# Load_Cell_Acquisition.net
KiCad netlist of a schematic drawn in Altium Designer
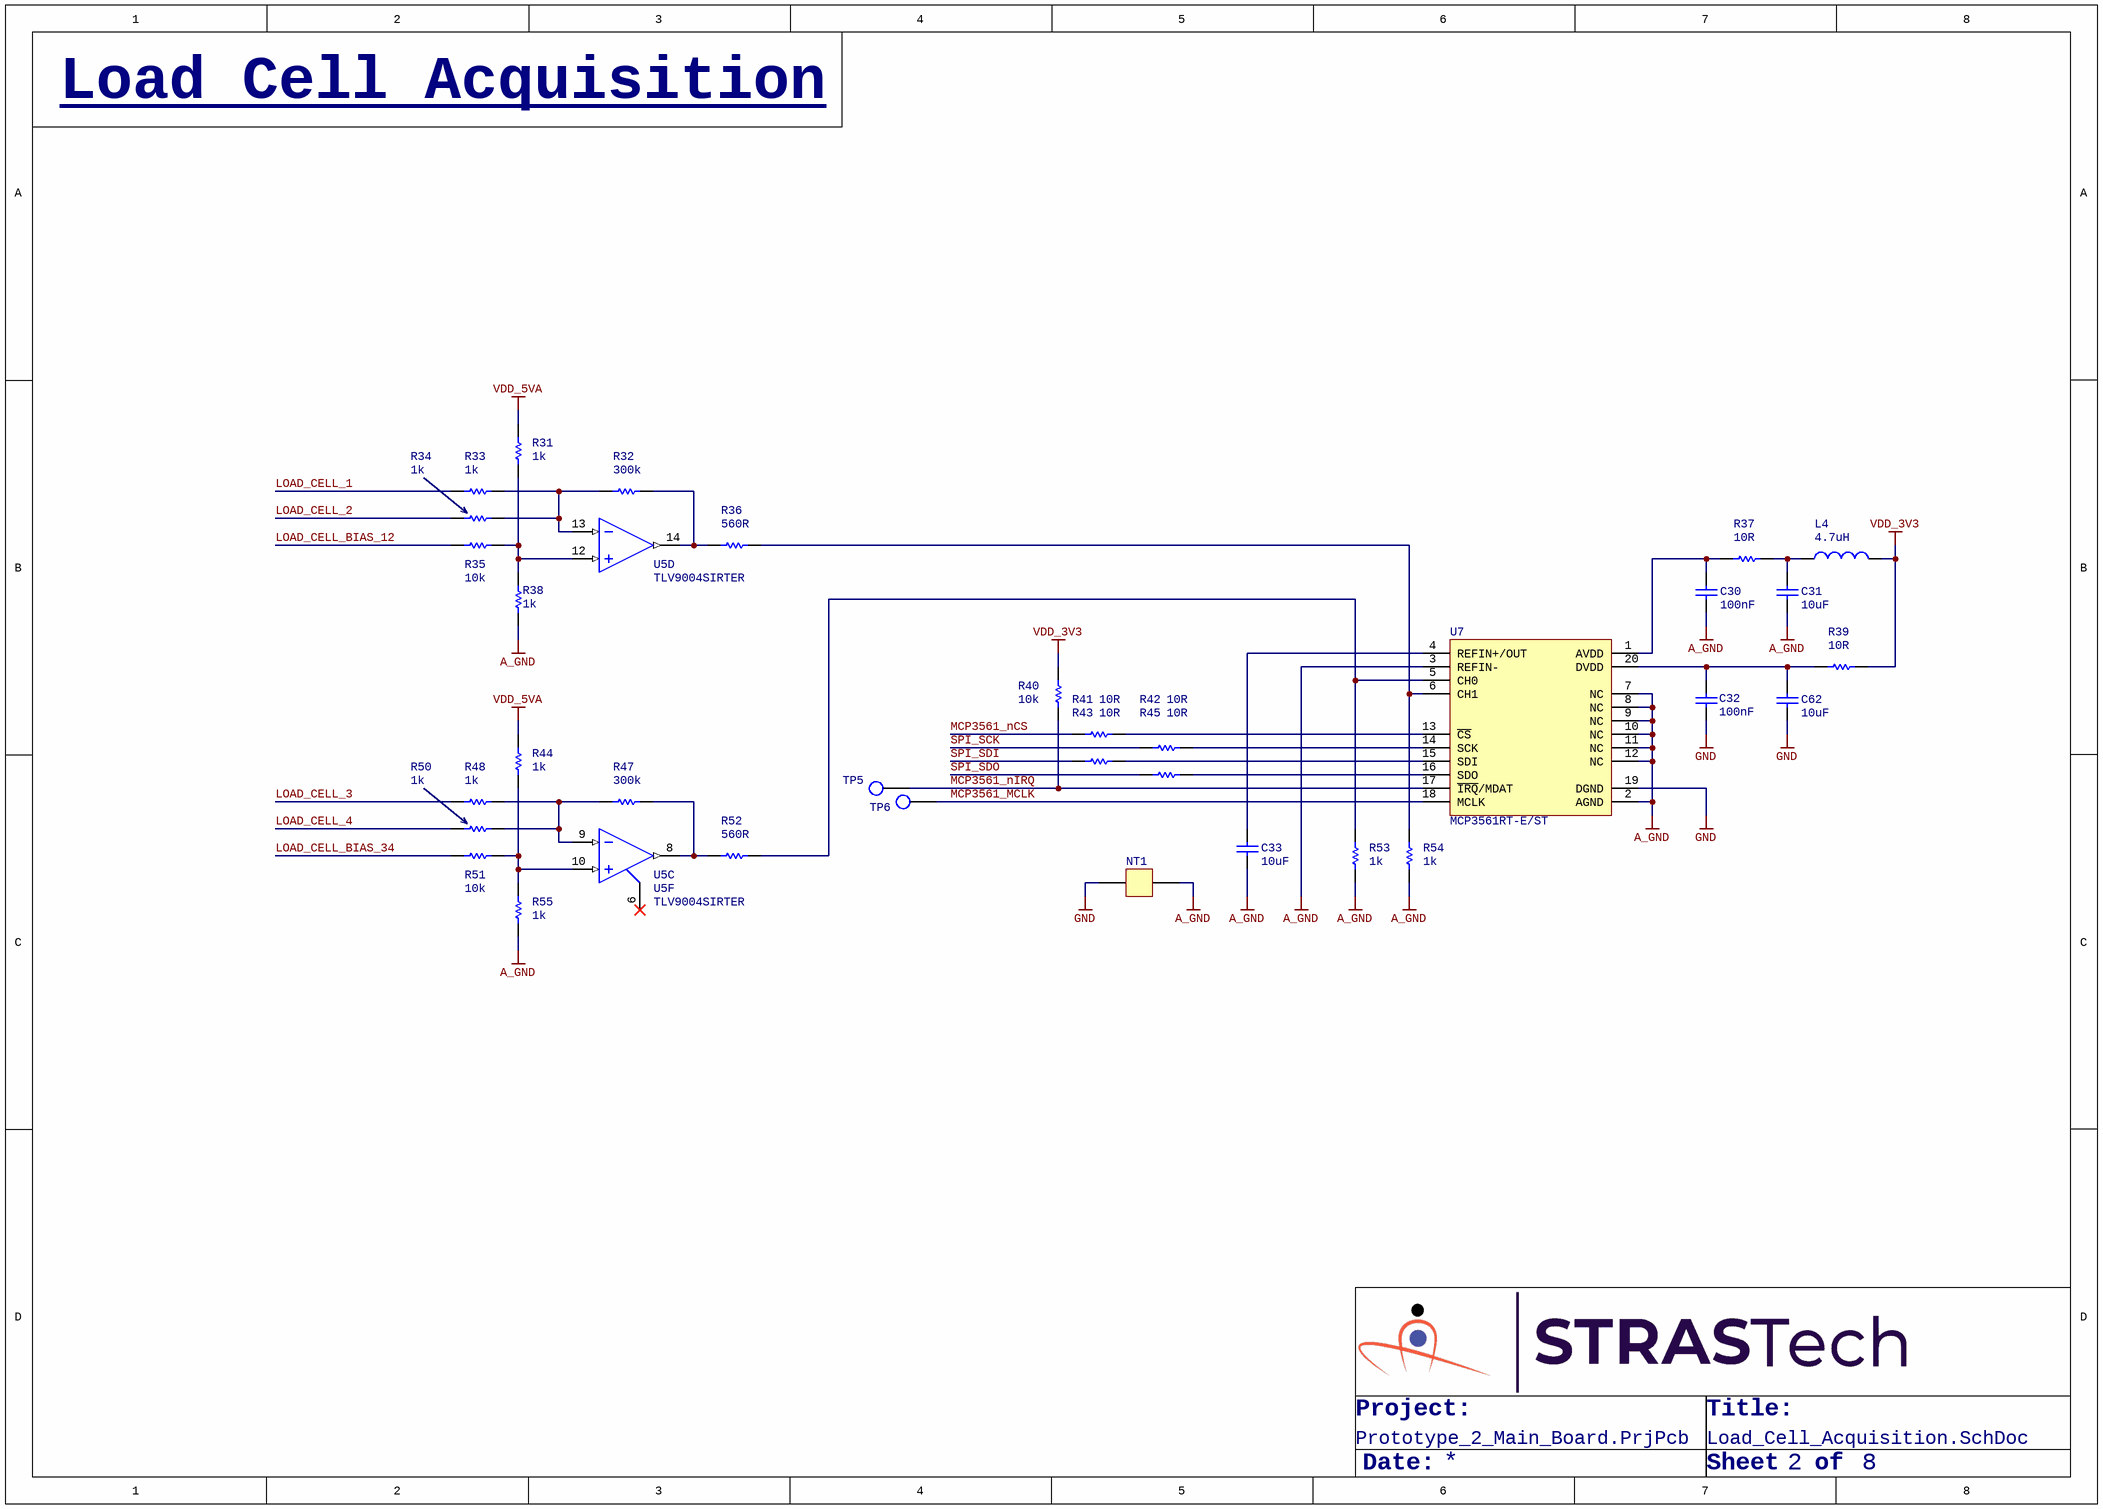
[diagram p0: Load_Cell_Acquisition.SchDoc]

(export (version "E")
  (design (tool "Eeschema 10.0.6"))
  (components
    (comp (ref "C30")
      (value "100nF")
      (footprint "Cap,SMD,0402")
      (description "0.1µF ±10% 25V Ceramic Capacitor X7R 0402 (1005 Metric)")
      (fields
        (field (name "VENDOR PART NUMBER") "490-14603-1-ND")
        (field (name "MANUFACTURER") "Murata Electronics")
        (field (name "CREATEDBY") "Judd Foster")
      )
      (libsource (lib "symbols") (part "CAP,Cer,100nF,25VDC,X7R,0402"))
    )
    (comp (ref "C31")
      (value "10uF")
      (footprint "Cap,SMD,0402")
      (description "10 µF ±20% 10V Ceramic Capacitor X5R 0402 (1005 Metric)")
      (fields
        (field (name "VENDOR PART NUMBER") "1276-1450-1-ND")
        (field (name "MANUFACTURER") "Samsung Electro-Mechanics")
        (field (name "CREATEDBY") "Judd Foster")
      )
      (libsource (lib "symbols") (part "CAP,Cer,10uF,10VDC,X5R,0402"))
    )
    (comp (ref "C32")
      (value "100nF")
      (footprint "Cap,SMD,0402")
      (description "0.1µF ±10% 25V Ceramic Capacitor X7R 0402 (1005 Metric)")
      (fields
        (field (name "VENDOR PART NUMBER") "490-14603-1-ND")
        (field (name "MANUFACTURER") "Murata Electronics")
        (field (name "CREATEDBY") "Judd Foster")
      )
      (libsource (lib "symbols") (part "CAP,Cer,100nF,25VDC,X7R,0402"))
    )
    (comp (ref "C33")
      (value "10uF")
      (footprint "Cap,SMD,0402")
      (description "10 µF ±20% 10V Ceramic Capacitor X5R 0402 (1005 Metric)")
      (fields
        (field (name "VENDOR PART NUMBER") "1276-1450-1-ND")
        (field (name "MANUFACTURER") "Samsung Electro-Mechanics")
        (field (name "CREATEDBY") "Judd Foster")
      )
      (libsource (lib "symbols") (part "CAP,Cer,10uF,10VDC,X5R,0402"))
    )
    (comp (ref "C62")
      (value "10uF")
      (footprint "Cap,SMD,0402")
      (description "10 µF ±20% 10V Ceramic Capacitor X5R 0402 (1005 Metric)")
      (fields
        (field (name "VENDOR PART NUMBER") "1276-1450-1-ND")
        (field (name "MANUFACTURER") "Samsung Electro-Mechanics")
        (field (name "CREATEDBY") "Judd Foster")
      )
      (libsource (lib "symbols") (part "CAP,Cer,10uF,10VDC,X5R,0402"))
    )
    (comp (ref "L4")
      (value "4.7uH")
      (footprint "IND,0805")
      (description "4.7 µH Shielded Multilayer Inductor 80 mA 300mOhm 0805 (2012 Metric)")
      (fields
        (field (name "VENDOR PART NUMBER") "445-3169-1-ND")
        (field (name "MANUFACTURER") "TDK Corporation")
        (field (name "CREATEDBY") "Judd Foster")
      )
      (libsource (lib "symbols") (part "IND,4.7uH,80mA,Multilayer,0805"))
    )
    (comp (ref "NT1")
      (value "Net Tie")
      (footprint "Net Tie,20x60mil")
      (fields (field (name "CREATEDBY") "Makan Mousavi"))
      (libsource (lib "symbols") (part "Net Tie"))
    )
    (comp (ref "R31")
      (value "1k")
      (footprint "RES,0402")
      (description "1 kOhms ±5% 0.063W, 1/16W Chip Resistor 0402 (1005 Metric) Automotive AEC-Q200 Thick Film")
      (fields
        (field (name "VENDOR PART NUMBER") "RMCF0402JT1K00CT-ND")
        (field (name "MANUFACTURER") "Stackpole Electronics Inc")
        (field (name "CREATEDBY") "Judd Foster")
      )
      (libsource (lib "symbols") (part "RES,1k,5%,0.063W,0402"))
    )
    (comp (ref "R32")
      (value "300k")
      (footprint "RES,0402")
      (description "300 kOhms ±1% 0.063W, 1/16W Chip Resistor 0402 (1005 Metric) Automotive AEC-Q200 Thick Film")
      (fields
        (field (name "MANUFACTURER") "Stackpole Electronics Inc")
        (field (name "MANUFACTURER PART NUMBER") "RMCF0402FT300K")
        (field (name "CREATEDBY") "Judd Foster")
      )
      (libsource (lib "symbols") (part "RES,300k,1%,0.063W,0402"))
    )
    (comp (ref "R33")
      (value "1k")
      (footprint "RES,0402")
      (description "1 kOhms ±5% 0.063W, 1/16W Chip Resistor 0402 (1005 Metric) Automotive AEC-Q200 Thick Film")
      (fields
        (field (name "VENDOR PART NUMBER") "RMCF0402JT1K00CT-ND")
        (field (name "MANUFACTURER") "Stackpole Electronics Inc")
        (field (name "CREATEDBY") "Judd Foster")
      )
      (libsource (lib "symbols") (part "RES,1k,5%,0.063W,0402"))
    )
    (comp (ref "R34")
      (value "1k")
      (footprint "RES,0402")
      (description "1 kOhms ±5% 0.063W, 1/16W Chip Resistor 0402 (1005 Metric) Automotive AEC-Q200 Thick Film")
      (fields
        (field (name "VENDOR PART NUMBER") "RMCF0402JT1K00CT-ND")
        (field (name "MANUFACTURER") "Stackpole Electronics Inc")
        (field (name "CREATEDBY") "Judd Foster")
      )
      (libsource (lib "symbols") (part "RES,1k,5%,0.063W,0402"))
    )
    (comp (ref "R35")
      (value "10k")
      (footprint "RES,0402")
      (description "10 kOhms ±5% 0.063W, 1/16W Chip Resistor 0402 (1005 Metric) Automotive AEC-Q200 Thick Film")
      (fields
        (field (name "VENDOR PART NUMBER") "RMCF0402JT10K0CT-ND")
        (field (name "MANUFACTURER") "Stackpole Electronics Inc")
        (field (name "CREATEDBY") "Judd Foster")
      )
      (libsource (lib "symbols") (part "RES,10k,5%,0.063W,0402"))
    )
    (comp (ref "R36")
      (value "560R")
      (footprint "RES,0402")
      (fields
        (field (name "MANUFACTURER") "TE Connectivity Passive Product")
        (field (name "MANUFACTURER PART NUMBER") "CRGCQ0402F560R")
        (field (name "VENDOR PART NUMBER") "A129624CT-ND")
        (field (name "CREATEDBY") "Judd Foster")
      )
      (libsource (lib "symbols") (part "RES,560R,1%,0.063W,0402"))
    )
    (comp (ref "R37")
      (value "10R")
      (footprint "RES,0402")
      (description "10 Ohms ±1% 0.063W, 1/16W Chip Resistor 0402 (1005 Metric) Automotive AEC-Q200 Thick Film")
      (fields
        (field (name "MANUFACTURER") "Panasonic Electronic Components")
        (field (name "MANUFACTURER PART NUMBER") "ERJ-2RKF10R0X")
        (field (name "CREATEDBY") "Judd Foster")
      )
      (libsource (lib "symbols") (part "RES,10R,1%,0.063W,0402"))
    )
    (comp (ref "R38")
      (value "1k")
      (footprint "RES,0402")
      (description "1 kOhms ±5% 0.063W, 1/16W Chip Resistor 0402 (1005 Metric) Automotive AEC-Q200 Thick Film")
      (fields
        (field (name "VENDOR PART NUMBER") "RMCF0402JT1K00CT-ND")
        (field (name "MANUFACTURER") "Stackpole Electronics Inc")
        (field (name "CREATEDBY") "Judd Foster")
      )
      (libsource (lib "symbols") (part "RES,1k,5%,0.063W,0402"))
    )
    (comp (ref "R39")
      (value "10R")
      (footprint "RES,0402")
      (description "10 Ohms ±1% 0.063W, 1/16W Chip Resistor 0402 (1005 Metric) Automotive AEC-Q200 Thick Film")
      (fields
        (field (name "MANUFACTURER") "Panasonic Electronic Components")
        (field (name "MANUFACTURER PART NUMBER") "ERJ-2RKF10R0X")
        (field (name "CREATEDBY") "Judd Foster")
      )
      (libsource (lib "symbols") (part "RES,10R,1%,0.063W,0402"))
    )
    (comp (ref "R40")
      (value "10k")
      (footprint "RES,0402")
      (description "10 kOhms ±5% 0.063W, 1/16W Chip Resistor 0402 (1005 Metric) Automotive AEC-Q200 Thick Film")
      (fields
        (field (name "VENDOR PART NUMBER") "RMCF0402JT10K0CT-ND")
        (field (name "MANUFACTURER") "Stackpole Electronics Inc")
        (field (name "CREATEDBY") "Judd Foster")
      )
      (libsource (lib "symbols") (part "RES,10k,5%,0.063W,0402"))
    )
    (comp (ref "R41")
      (value "10R")
      (footprint "RES,0402")
      (description "10 Ohms ±1% 0.063W, 1/16W Chip Resistor 0402 (1005 Metric) Automotive AEC-Q200 Thick Film")
      (fields
        (field (name "MANUFACTURER") "Panasonic Electronic Components")
        (field (name "MANUFACTURER PART NUMBER") "ERJ-2RKF10R0X")
        (field (name "CREATEDBY") "Judd Foster")
      )
      (libsource (lib "symbols") (part "RES,10R,1%,0.063W,0402"))
    )
    (comp (ref "R42")
      (value "10R")
      (footprint "RES,0402")
      (description "10 Ohms ±1% 0.063W, 1/16W Chip Resistor 0402 (1005 Metric) Automotive AEC-Q200 Thick Film")
      (fields
        (field (name "MANUFACTURER") "Panasonic Electronic Components")
        (field (name "MANUFACTURER PART NUMBER") "ERJ-2RKF10R0X")
        (field (name "CREATEDBY") "Judd Foster")
      )
      (libsource (lib "symbols") (part "RES,10R,1%,0.063W,0402"))
    )
    (comp (ref "R43")
      (value "10R")
      (footprint "RES,0402")
      (description "10 Ohms ±1% 0.063W, 1/16W Chip Resistor 0402 (1005 Metric) Automotive AEC-Q200 Thick Film")
      (fields
        (field (name "MANUFACTURER") "Panasonic Electronic Components")
        (field (name "MANUFACTURER PART NUMBER") "ERJ-2RKF10R0X")
        (field (name "CREATEDBY") "Judd Foster")
      )
      (libsource (lib "symbols") (part "RES,10R,1%,0.063W,0402"))
    )
    (comp (ref "R44")
      (value "1k")
      (footprint "RES,0402")
      (description "1 kOhms ±5% 0.063W, 1/16W Chip Resistor 0402 (1005 Metric) Automotive AEC-Q200 Thick Film")
      (fields
        (field (name "VENDOR PART NUMBER") "RMCF0402JT1K00CT-ND")
        (field (name "MANUFACTURER") "Stackpole Electronics Inc")
        (field (name "CREATEDBY") "Judd Foster")
      )
      (libsource (lib "symbols") (part "RES,1k,5%,0.063W,0402"))
    )
    (comp (ref "R45")
      (value "10R")
      (footprint "RES,0402")
      (description "10 Ohms ±1% 0.063W, 1/16W Chip Resistor 0402 (1005 Metric) Automotive AEC-Q200 Thick Film")
      (fields
        (field (name "MANUFACTURER") "Panasonic Electronic Components")
        (field (name "MANUFACTURER PART NUMBER") "ERJ-2RKF10R0X")
        (field (name "CREATEDBY") "Judd Foster")
      )
      (libsource (lib "symbols") (part "RES,10R,1%,0.063W,0402"))
    )
    (comp (ref "R47")
      (value "300k")
      (footprint "RES,0402")
      (description "300 kOhms ±1% 0.063W, 1/16W Chip Resistor 0402 (1005 Metric) Automotive AEC-Q200 Thick Film")
      (fields
        (field (name "MANUFACTURER") "Stackpole Electronics Inc")
        (field (name "MANUFACTURER PART NUMBER") "RMCF0402FT300K")
        (field (name "CREATEDBY") "Judd Foster")
      )
      (libsource (lib "symbols") (part "RES,300k,1%,0.063W,0402"))
    )
    (comp (ref "R48")
      (value "1k")
      (footprint "RES,0402")
      (description "1 kOhms ±5% 0.063W, 1/16W Chip Resistor 0402 (1005 Metric) Automotive AEC-Q200 Thick Film")
      (fields
        (field (name "VENDOR PART NUMBER") "RMCF0402JT1K00CT-ND")
        (field (name "MANUFACTURER") "Stackpole Electronics Inc")
        (field (name "CREATEDBY") "Judd Foster")
      )
      (libsource (lib "symbols") (part "RES,1k,5%,0.063W,0402"))
    )
    (comp (ref "R50")
      (value "1k")
      (footprint "RES,0402")
      (description "1 kOhms ±5% 0.063W, 1/16W Chip Resistor 0402 (1005 Metric) Automotive AEC-Q200 Thick Film")
      (fields
        (field (name "VENDOR PART NUMBER") "RMCF0402JT1K00CT-ND")
        (field (name "MANUFACTURER") "Stackpole Electronics Inc")
        (field (name "CREATEDBY") "Judd Foster")
      )
      (libsource (lib "symbols") (part "RES,1k,5%,0.063W,0402"))
    )
    (comp (ref "R51")
      (value "10k")
      (footprint "RES,0402")
      (description "10 kOhms ±5% 0.063W, 1/16W Chip Resistor 0402 (1005 Metric) Automotive AEC-Q200 Thick Film")
      (fields
        (field (name "VENDOR PART NUMBER") "RMCF0402JT10K0CT-ND")
        (field (name "MANUFACTURER") "Stackpole Electronics Inc")
        (field (name "CREATEDBY") "Judd Foster")
      )
      (libsource (lib "symbols") (part "RES,10k,5%,0.063W,0402"))
    )
    (comp (ref "R52")
      (value "560R")
      (footprint "RES,0402")
      (fields
        (field (name "MANUFACTURER") "TE Connectivity Passive Product")
        (field (name "MANUFACTURER PART NUMBER") "CRGCQ0402F560R")
        (field (name "VENDOR PART NUMBER") "A129624CT-ND")
        (field (name "CREATEDBY") "Judd Foster")
      )
      (libsource (lib "symbols") (part "RES,560R,1%,0.063W,0402"))
    )
    (comp (ref "R53")
      (value "1k")
      (footprint "RES,0402")
      (description "1 kOhms ±5% 0.063W, 1/16W Chip Resistor 0402 (1005 Metric) Automotive AEC-Q200 Thick Film")
      (fields
        (field (name "VENDOR PART NUMBER") "RMCF0402JT1K00CT-ND")
        (field (name "MANUFACTURER") "Stackpole Electronics Inc")
        (field (name "CREATEDBY") "Judd Foster")
      )
      (libsource (lib "symbols") (part "RES,1k,5%,0.063W,0402"))
    )
    (comp (ref "R54")
      (value "1k")
      (footprint "RES,0402")
      (description "1 kOhms ±5% 0.063W, 1/16W Chip Resistor 0402 (1005 Metric) Automotive AEC-Q200 Thick Film")
      (fields
        (field (name "VENDOR PART NUMBER") "RMCF0402JT1K00CT-ND")
        (field (name "MANUFACTURER") "Stackpole Electronics Inc")
        (field (name "CREATEDBY") "Judd Foster")
      )
      (libsource (lib "symbols") (part "RES,1k,5%,0.063W,0402"))
    )
    (comp (ref "R55")
      (value "1k")
      (footprint "RES,0402")
      (description "1 kOhms ±5% 0.063W, 1/16W Chip Resistor 0402 (1005 Metric) Automotive AEC-Q200 Thick Film")
      (fields
        (field (name "VENDOR PART NUMBER") "RMCF0402JT1K00CT-ND")
        (field (name "MANUFACTURER") "Stackpole Electronics Inc")
        (field (name "CREATEDBY") "Judd Foster")
      )
      (libsource (lib "symbols") (part "RES,1k,5%,0.063W,0402"))
    )
    (comp (ref "TP5")
      (value "TESTPOINT")
      (footprint "testpoint,smd,round,1mm")
      (description "PCB Testpoint")
      (fields (field (name "CREATEDBY") "Judd Foster"))
      (libsource (lib "symbols") (part "TESTPOINT"))
    )
    (comp (ref "TP6")
      (value "TESTPOINT")
      (footprint "testpoint,smd,round,1mm")
      (description "PCB Testpoint")
      (fields (field (name "CREATEDBY") "Judd Foster"))
      (libsource (lib "symbols") (part "TESTPOINT"))
    )
    (comp (ref "U5")
      (value "TLV9004SIRTER")
      (footprint "IC,QFN-16,3x3")
      (description "General Purpose Amplifier 4 Circuit Rail-to-Rail 16-WQFN (3x3)")
      (fields
        (field (name "MANUFACTURER") "Texas Instruments")
        (field (name "VENDOR PART NUMBER") "296-51829-1-ND")
        (field (name "CREATEDBY") "Judd Foster")
      )
      (libsource (lib "symbols") (part "TLV9004SIRTER"))
    )
    (comp (ref "U7")
      (value "MCP3561RT-E/ST")
      (footprint "IC,TSSOP-20,W4.4")
      (description "24 Bit Analog to Digital Converter 1 Input 1 Sigma-Delta 20-TSSOP")
      (fields
        (field (name "VENDOR PART NUMBER") "150-MCP3561RT-E/STCT-ND")
        (field (name "MANUFACTURER") "Microchip Technology")
        (field (name "CREATEDBY") "Judd Foster")
      )
      (libsource (lib "symbols") (part "MCP3561RT-E/ST"))
    )
  )
  (nets
    (net (code "1") (name "/LOAD_CELL_1") (class "Default")
      (node (ref "R33") (pin "2") (pinfunction "2_2") (pintype "passive"))
    )
    (net (code "2") (name "/LOAD_CELL_2") (class "Default")
      (node (ref "R34") (pin "2") (pinfunction "2_2") (pintype "passive"))
    )
    (net (code "3") (name "/LOAD_CELL_3") (class "Default")
      (node (ref "R48") (pin "2") (pinfunction "2_2") (pintype "passive"))
    )
    (net (code "4") (name "/LOAD_CELL_4") (class "Default")
      (node (ref "R50") (pin "2") (pinfunction "2_2") (pintype "passive"))
    )
    (net (code "5") (name "/LOAD_CELL_BIAS_12") (class "Default")
      (node (ref "R35") (pin "1") (pinfunction "1_1") (pintype "passive"))
    )
    (net (code "6") (name "/LOAD_CELL_BIAS_34") (class "Default")
      (node (ref "R51") (pin "1") (pinfunction "1_1") (pintype "passive"))
    )
    (net (code "7") (name "/MCP3561_MCLK") (class "Default")
      (node (ref "TP6") (pin "1") (pinfunction "TP_1") (pintype "passive"))
      (node (ref "U7") (pin "18") (pinfunction "MCLK_18") (pintype "passive"))
    )
    (net (code "8") (name "/MCP3561_nCS") (class "Default")
      (node (ref "R41") (pin "1") (pinfunction "1_1") (pintype "passive"))
    )
    (net (code "9") (name "/MCP3561_nIRQ") (class "Default")
      (node (ref "R40") (pin "1") (pinfunction "1_1") (pintype "passive"))
      (node (ref "TP5") (pin "1") (pinfunction "TP_1") (pintype "passive"))
      (node (ref "U7") (pin "17") (pinfunction "~{IRQ}/MDAT_17") (pintype "passive"))
    )
    (net (code "10") (name "/SPI_SCK") (class "Default")
      (node (ref "R42") (pin "1") (pinfunction "1_1") (pintype "passive"))
    )
    (net (code "11") (name "/SPI_SDI") (class "Default")
      (node (ref "R43") (pin "1") (pinfunction "1_1") (pintype "passive"))
    )
    (net (code "12") (name "/SPI_SDO") (class "Default")
      (node (ref "R45") (pin "1") (pinfunction "1_1") (pintype "passive"))
    )
    (net (code "13") (name "A_GND") (class "Default")
      (node (ref "C30") (pin "1") (pinfunction "1_1") (pintype "passive"))
      (node (ref "C31") (pin "2") (pinfunction "2_2") (pintype "passive"))
      (node (ref "C33") (pin "1") (pinfunction "1_1") (pintype "passive"))
      (node (ref "NT1") (pin "2") (pinfunction "2_2") (pintype "passive"))
      (node (ref "R38") (pin "1") (pinfunction "1_1") (pintype "passive"))
      (node (ref "R53") (pin "2") (pinfunction "2_2") (pintype "passive"))
      (node (ref "R54") (pin "2") (pinfunction "2_2") (pintype "passive"))
      (node (ref "R55") (pin "1") (pinfunction "1_1") (pintype "passive"))
      (node (ref "U7") (pin "10") (pinfunction "NC_10") (pintype "passive"))
      (node (ref "U7") (pin "11") (pinfunction "NC_11") (pintype "passive"))
      (node (ref "U7") (pin "12") (pinfunction "NC_12") (pintype "passive"))
      (node (ref "U7") (pin "2") (pinfunction "AGND_2") (pintype "passive"))
      (node (ref "U7") (pin "3") (pinfunction "REFIN-_3") (pintype "passive"))
      (node (ref "U7") (pin "7") (pinfunction "NC_7") (pintype "passive"))
      (node (ref "U7") (pin "8") (pinfunction "NC_8") (pintype "passive"))
      (node (ref "U7") (pin "9") (pinfunction "NC_9") (pintype "passive"))
    )
    (net (code "14") (name "GND") (class "Default")
      (node (ref "C32") (pin "1") (pinfunction "1_1") (pintype "passive"))
      (node (ref "C62") (pin "2") (pinfunction "2_2") (pintype "passive"))
      (node (ref "NT1") (pin "1") (pinfunction "1_1") (pintype "passive"))
      (node (ref "U7") (pin "19") (pinfunction "DGND_19") (pintype "passive"))
    )
    (net (code "15") (name "Net-(C31-Pad1)") (class "Default")
      (node (ref "C31") (pin "1") (pinfunction "1_1") (pintype "passive"))
      (node (ref "L4") (pin "1") (pinfunction "1_1") (pintype "passive"))
      (node (ref "R37") (pin "2") (pinfunction "2_2") (pintype "passive"))
    )
    (net (code "16") (name "Net-(U5C-IN3+)") (class "Default")
      (node (ref "R44") (pin "1") (pinfunction "1_1") (pintype "passive"))
      (node (ref "R51") (pin "2") (pinfunction "2_2") (pintype "passive"))
      (node (ref "R55") (pin "2") (pinfunction "2_2") (pintype "passive"))
      (node (ref "U5") (pin "10") (pinfunction "IN3+_10") (pintype "input"))
    )
    (net (code "17") (name "Net-(U5C-IN3-)") (class "Default")
      (node (ref "R47") (pin "2") (pinfunction "2_2") (pintype "passive"))
      (node (ref "R48") (pin "1") (pinfunction "1_1") (pintype "passive"))
      (node (ref "R50") (pin "1") (pinfunction "1_1") (pintype "passive"))
      (node (ref "U5") (pin "9") (pinfunction "IN3-_9") (pintype "input"))
    )
    (net (code "18") (name "Net-(U5C-OUT3)") (class "Default")
      (node (ref "R47") (pin "1") (pinfunction "1_1") (pintype "passive"))
      (node (ref "R52") (pin "2") (pinfunction "2_2") (pintype "passive"))
      (node (ref "U5") (pin "8") (pinfunction "OUT3_8") (pintype "output"))
    )
    (net (code "19") (name "Net-(U5D-IN4+)") (class "Default")
      (node (ref "R31") (pin "1") (pinfunction "1_1") (pintype "passive"))
      (node (ref "R35") (pin "2") (pinfunction "2_2") (pintype "passive"))
      (node (ref "R38") (pin "2") (pinfunction "2_2") (pintype "passive"))
      (node (ref "U5") (pin "12") (pinfunction "IN4+_12") (pintype "input"))
    )
    (net (code "20") (name "Net-(U5D-IN4-)") (class "Default")
      (node (ref "R32") (pin "2") (pinfunction "2_2") (pintype "passive"))
      (node (ref "R33") (pin "1") (pinfunction "1_1") (pintype "passive"))
      (node (ref "R34") (pin "1") (pinfunction "1_1") (pintype "passive"))
      (node (ref "U5") (pin "13") (pinfunction "IN4-_13") (pintype "input"))
    )
    (net (code "21") (name "Net-(U5D-OUT4)") (class "Default")
      (node (ref "R32") (pin "1") (pinfunction "1_1") (pintype "passive"))
      (node (ref "R36") (pin "2") (pinfunction "2_2") (pintype "passive"))
      (node (ref "U5") (pin "14") (pinfunction "OUT4_14") (pintype "output"))
    )
    (net (code "22") (name "Net-(U7-AVDD)") (class "Default")
      (node (ref "C30") (pin "2") (pinfunction "2_2") (pintype "passive"))
      (node (ref "R37") (pin "1") (pinfunction "1_1") (pintype "passive"))
      (node (ref "U7") (pin "1") (pinfunction "AVDD_1") (pintype "passive"))
    )
    (net (code "23") (name "Net-(U7-CH0)") (class "Default")
      (node (ref "R52") (pin "1") (pinfunction "1_1") (pintype "passive"))
      (node (ref "R53") (pin "1") (pinfunction "1_1") (pintype "passive"))
      (node (ref "U7") (pin "5") (pinfunction "CH0_5") (pintype "passive"))
    )
    (net (code "24") (name "Net-(U7-CH1)") (class "Default")
      (node (ref "R36") (pin "1") (pinfunction "1_1") (pintype "passive"))
      (node (ref "R54") (pin "1") (pinfunction "1_1") (pintype "passive"))
      (node (ref "U7") (pin "6") (pinfunction "CH1_6") (pintype "passive"))
    )
    (net (code "25") (name "Net-(U7-DVDD)") (class "Default")
      (node (ref "C32") (pin "2") (pinfunction "2_2") (pintype "passive"))
      (node (ref "C62") (pin "1") (pinfunction "1_1") (pintype "passive"))
      (node (ref "R39") (pin "1") (pinfunction "1_1") (pintype "passive"))
      (node (ref "U7") (pin "20") (pinfunction "DVDD_20") (pintype "passive"))
    )
    (net (code "26") (name "Net-(U7-REFIN+{slash}OUT)") (class "Default")
      (node (ref "C33") (pin "2") (pinfunction "2_2") (pintype "passive"))
      (node (ref "U7") (pin "4") (pinfunction "REFIN+/OUT_4") (pintype "passive"))
    )
    (net (code "27") (name "Net-(U7-SCK)") (class "Default")
      (node (ref "R42") (pin "2") (pinfunction "2_2") (pintype "passive"))
      (node (ref "U7") (pin "14") (pinfunction "SCK_14") (pintype "passive"))
    )
    (net (code "28") (name "Net-(U7-SDI)") (class "Default")
      (node (ref "R43") (pin "2") (pinfunction "2_2") (pintype "passive"))
      (node (ref "U7") (pin "15") (pinfunction "SDI_15") (pintype "passive"))
    )
    (net (code "29") (name "Net-(U7-SDO)") (class "Default")
      (node (ref "R45") (pin "2") (pinfunction "2_2") (pintype "passive"))
      (node (ref "U7") (pin "16") (pinfunction "SDO_16") (pintype "passive"))
    )
    (net (code "30") (name "Net-(U7-~{CS})") (class "Default")
      (node (ref "R41") (pin "2") (pinfunction "2_2") (pintype "passive"))
      (node (ref "U7") (pin "13") (pinfunction "~{CS}_13") (pintype "passive"))
    )
    (net (code "31") (name "VDD_3V3") (class "Default")
      (node (ref "L4") (pin "2") (pinfunction "2_2") (pintype "passive"))
      (node (ref "R39") (pin "2") (pinfunction "2_2") (pintype "passive"))
      (node (ref "R40") (pin "2") (pinfunction "2_2") (pintype "passive"))
    )
    (net (code "32") (name "VDD_5VA") (class "Default")
      (node (ref "R31") (pin "2") (pinfunction "2_2") (pintype "passive"))
      (node (ref "R44") (pin "2") (pinfunction "2_2") (pintype "passive"))
    )
    (net (code "33") (name "unconnected-(U5F-~{SHDN}12-Pad6)") (class "Default")
      (node (ref "U5") (pin "6") (pinfunction "~{SHDN}12_6") (pintype "power_in+no_connect"))
    )
  )
)
